# Led_7seg.net
KiCad netlist of a schematic drawn in Altium Designer
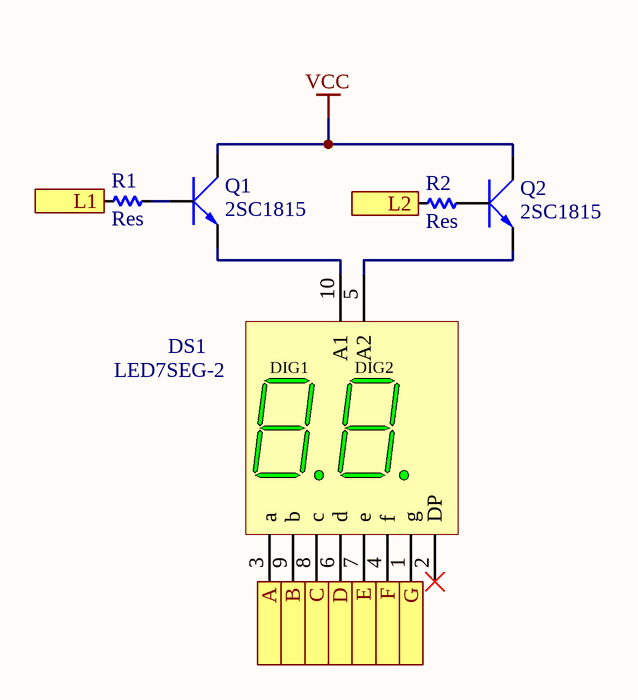
[diagram p0: Led_7seg.SchDoc]

(export (version "E")
  (design (tool "Eeschema 10.0.6"))
  (components
    (comp (ref "DS1")
      (value "LED7SEG-2")
      (footprint "LED7SEG-2-0.36")
      (description "9.2 mm Green 7-Segment Display: 2-Digit, RH DP")
      (fields (field (name "PUBLISHER") "Altium Limited"))
      (libsource (lib "APESLAB") (part "LED7SEG-2"))
    )
    (comp (ref "Q1")
      (value "2SC1815")
      (footprint "SOT23-321")
      (description "NPN 600mW, ECB")
      (libsource (lib "Devzone_SCHLib") (part "2SC1815"))
    )
    (comp (ref "Q2")
      (value "2SC1815")
      (footprint "SOT23-321")
      (description "NPN 600mW, ECB")
      (libsource (lib "APESLAB") (part "2SC1815"))
    )
    (comp (ref "R1")
      (value "Res")
      (footprint "RES-SMD-0101")
      (description "Resistor")
      (fields
        (field (name "MANUFACTURER") "Generic Components")
        (field (name "PUBLISHER") "Altium Hobart Technology Centre")
      )
      (libsource (lib "APESLAB") (part "Res-SMD"))
    )
    (comp (ref "R2")
      (value "Res")
      (footprint "RES-SMD-0101")
      (description "Resistor")
      (fields
        (field (name "MANUFACTURER") "Generic Components")
        (field (name "PUBLISHER") "Altium Hobart Technology Centre")
      )
      (libsource (lib "APESLAB") (part "Res-SMD"))
    )
  )
  (nets
    (net (code "1") (name "/A") (class "Default")
      (node (ref "DS1") (pin "3") (pinfunction "a_3") (pintype "passive"))
    )
    (net (code "2") (name "/B") (class "Default")
      (node (ref "DS1") (pin "9") (pinfunction "b_9") (pintype "passive"))
    )
    (net (code "3") (name "/C") (class "Default")
      (node (ref "DS1") (pin "8") (pinfunction "c_8") (pintype "passive"))
    )
    (net (code "4") (name "/D") (class "Default")
      (node (ref "DS1") (pin "6") (pinfunction "d_6") (pintype "passive"))
    )
    (net (code "5") (name "/E") (class "Default")
      (node (ref "DS1") (pin "7") (pinfunction "e_7") (pintype "passive"))
    )
    (net (code "6") (name "/F") (class "Default")
      (node (ref "DS1") (pin "4") (pinfunction "f_4") (pintype "passive"))
    )
    (net (code "7") (name "/G") (class "Default")
      (node (ref "DS1") (pin "1") (pinfunction "g_1") (pintype "passive"))
    )
    (net (code "8") (name "/L1") (class "Default")
      (node (ref "R1") (pin "1") (pinfunction "1_1") (pintype "passive"))
    )
    (net (code "9") (name "/L2") (class "Default")
      (node (ref "R2") (pin "1") (pinfunction "1_1") (pintype "passive"))
    )
    (net (code "10") (name "Net-(DS1-A1)") (class "Default")
      (node (ref "DS1") (pin "10") (pinfunction "A1_10") (pintype "passive"))
      (node (ref "Q1") (pin "1") (pinfunction "E_1") (pintype "passive"))
    )
    (net (code "11") (name "Net-(DS1-A2)") (class "Default")
      (node (ref "DS1") (pin "5") (pinfunction "A2_5") (pintype "passive"))
      (node (ref "Q2") (pin "1") (pinfunction "E_1") (pintype "passive"))
    )
    (net (code "12") (name "Net-(Q1-B)") (class "Default")
      (node (ref "Q1") (pin "3") (pinfunction "B_3") (pintype "passive"))
      (node (ref "R1") (pin "2") (pinfunction "2_2") (pintype "passive"))
    )
    (net (code "13") (name "Net-(Q2-B)") (class "Default")
      (node (ref "Q2") (pin "3") (pinfunction "B_3") (pintype "passive"))
      (node (ref "R2") (pin "2") (pinfunction "2_2") (pintype "passive"))
    )
    (net (code "14") (name "VCC") (class "Default")
      (node (ref "Q1") (pin "2") (pinfunction "C_2") (pintype "passive"))
      (node (ref "Q2") (pin "2") (pinfunction "C_2") (pintype "passive"))
    )
    (net (code "15") (name "unconnected-(DS1-DP-Pad2)") (class "Default")
      (node (ref "DS1") (pin "2") (pinfunction "DP_2") (pintype "passive+no_connect"))
    )
  )
)
